# Ak_ll__Ev.net
KiCad netlist of a schematic drawn in Altium Designer
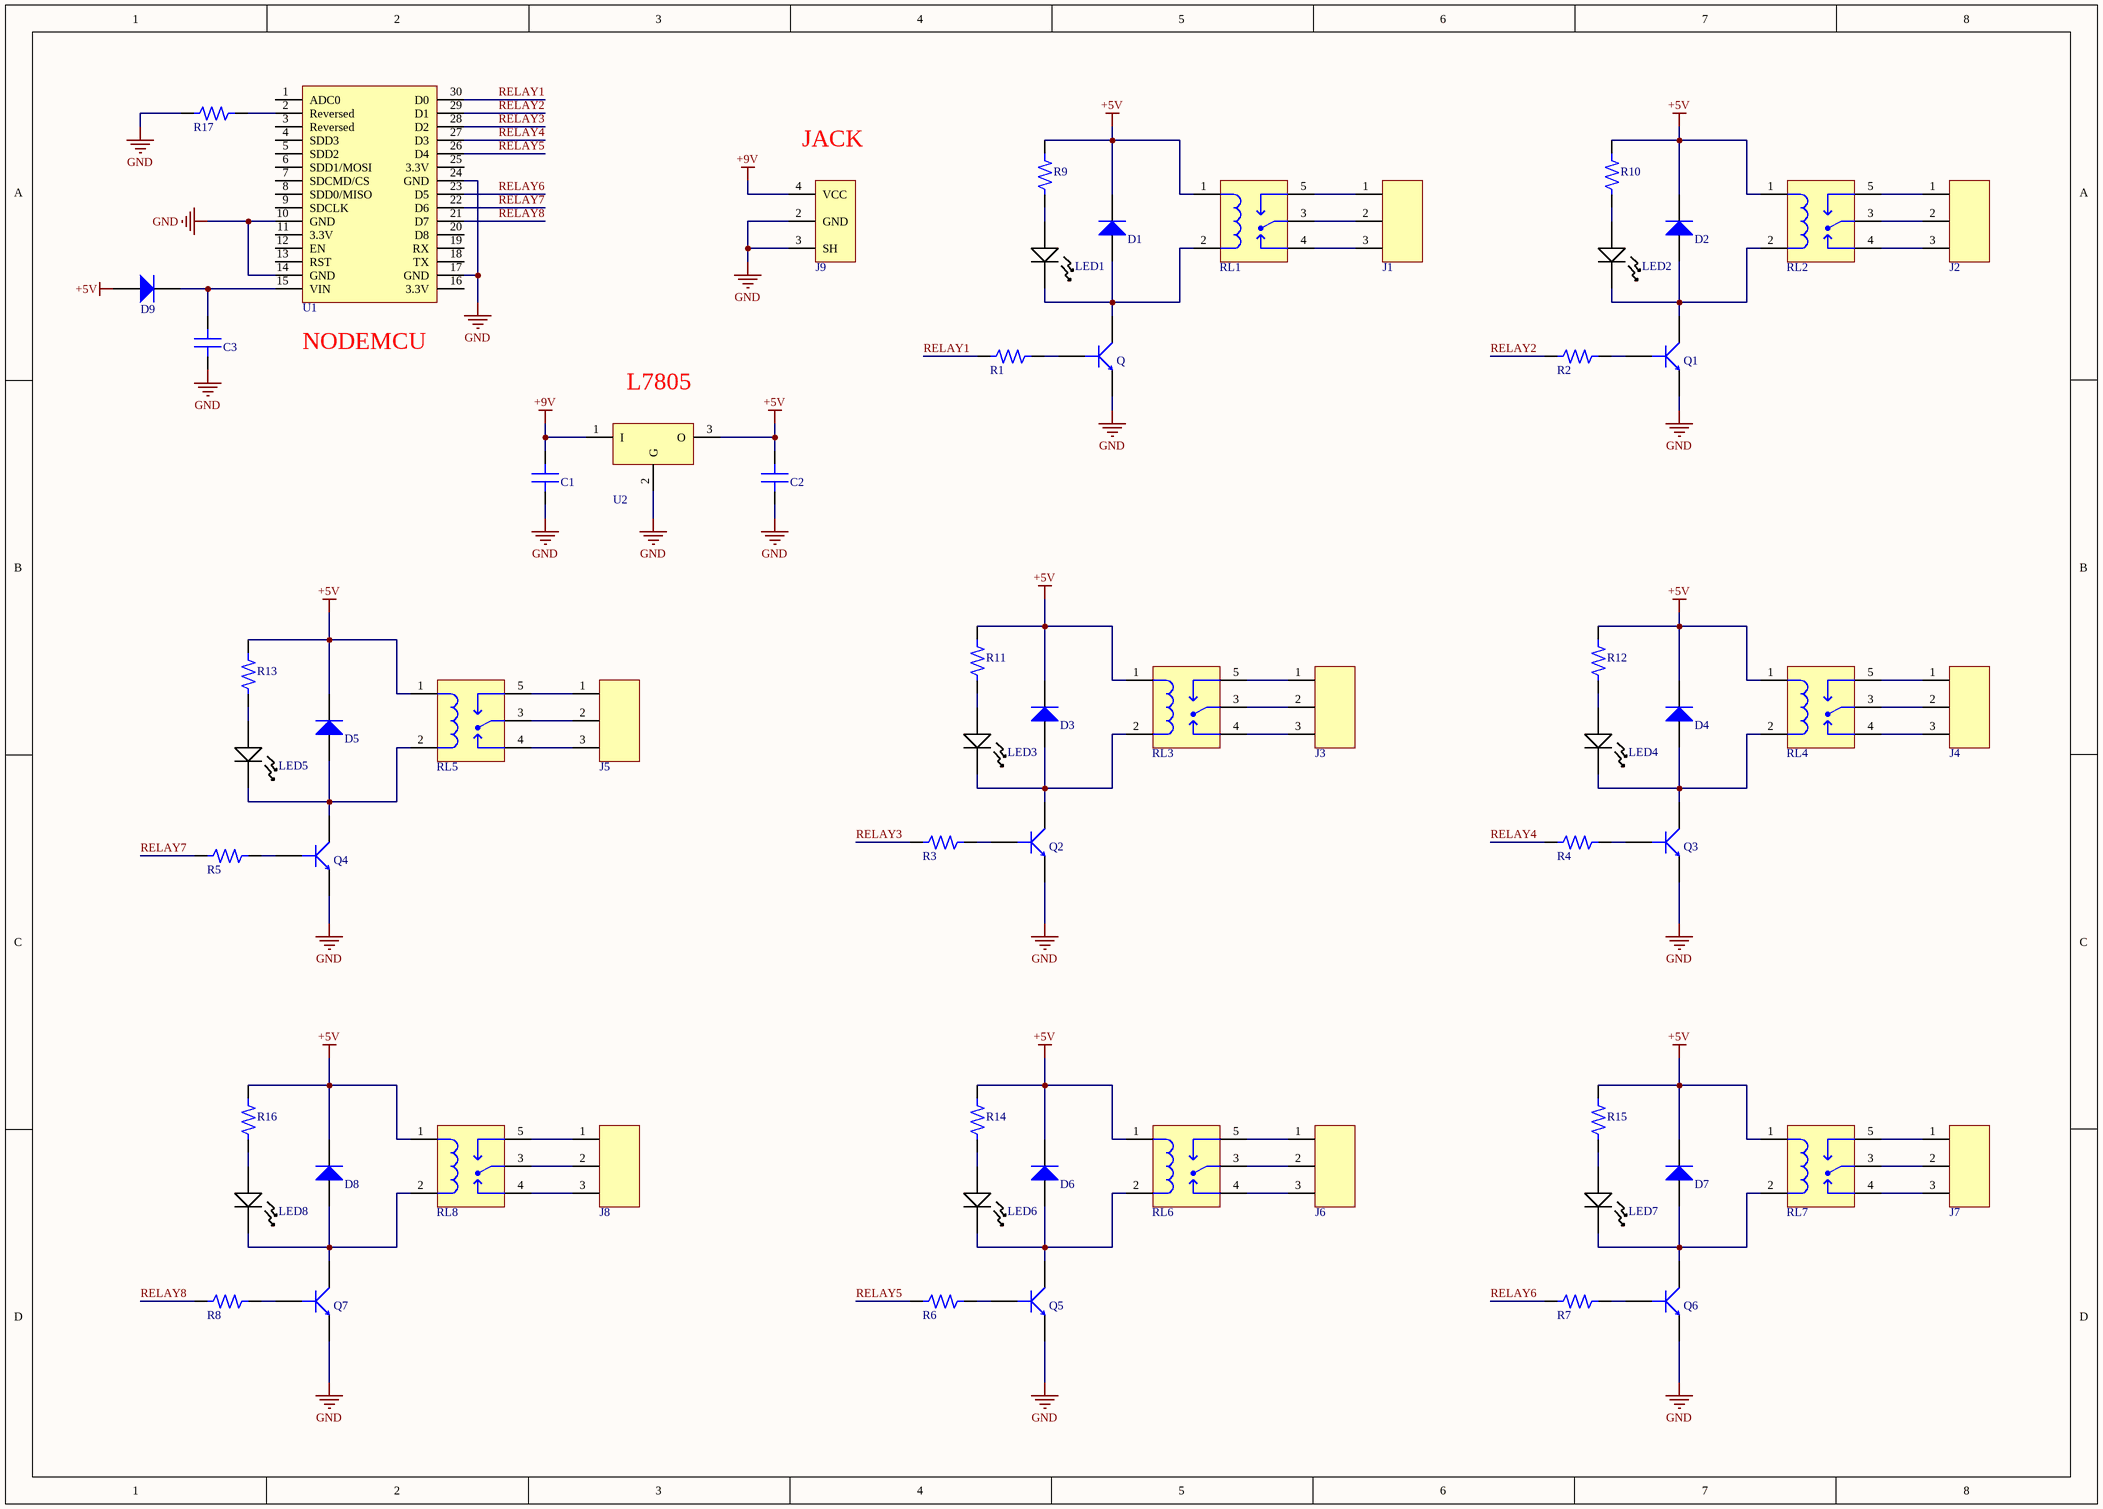
[diagram p0: Akıllı_Ev.SchDoc]

(export (version "E")
  (design (tool "Eeschema 10.0.6"))
  (components
    (comp (ref "C1") (value "100uF") (footprint "CAP 100uF") (libsource (lib "AKILLI_EV") (part "CAP 100uF")))
    (comp (ref "C2") (value "100uF") (footprint "CAP 100uF") (libsource (lib "AKILLI_EV") (part "CAP 100uF")))
    (comp (ref "C3") (value "100nF") (footprint "CAP 100nF") (libsource (lib "AKILLI_EV") (part "CAP 100nF")))
    (comp (ref "D1")
      (value "1N4007")
      (footprint "DIODE - 1N4007")
      (description "1N4007 Rectifier Diode 1 A 1000 V DO-41 Axial 4007 1 amp 1000 Volt Electronic Silicon Diodes")
      (libsource (lib "AKILLI_EV") (part "Diode 1N4007"))
    )
    (comp (ref "D2")
      (value "1N4007")
      (footprint "DIODE - 1N4007")
      (description "1N4007 Rectifier Diode 1 A 1000 V DO-41 Axial 4007 1 amp 1000 Volt Electronic Silicon Diodes")
      (libsource (lib "AKILLI_EV") (part "Diode 1N4007"))
    )
    (comp (ref "D3")
      (value "1N4007")
      (footprint "DIODE - 1N4007")
      (description "1N4007 Rectifier Diode 1 A 1000 V DO-41 Axial 4007 1 amp 1000 Volt Electronic Silicon Diodes")
      (libsource (lib "AKILLI_EV") (part "Diode 1N4007"))
    )
    (comp (ref "D4")
      (value "1N4007")
      (footprint "DIODE - 1N4007")
      (description "1N4007 Rectifier Diode 1 A 1000 V DO-41 Axial 4007 1 amp 1000 Volt Electronic Silicon Diodes")
      (libsource (lib "AKILLI_EV") (part "Diode 1N4007"))
    )
    (comp (ref "D5")
      (value "1N4007")
      (footprint "DIODE - 1N4007")
      (description "1N4007 Rectifier Diode 1 A 1000 V DO-41 Axial 4007 1 amp 1000 Volt Electronic Silicon Diodes")
      (libsource (lib "AKILLI_EV") (part "Diode 1N4007"))
    )
    (comp (ref "D6")
      (value "1N4007")
      (footprint "DIODE - 1N4007")
      (description "1N4007 Rectifier Diode 1 A 1000 V DO-41 Axial 4007 1 amp 1000 Volt Electronic Silicon Diodes")
      (libsource (lib "AKILLI_EV") (part "Diode 1N4007"))
    )
    (comp (ref "D7")
      (value "1N4007")
      (footprint "DIODE - 1N4007")
      (description "1N4007 Rectifier Diode 1 A 1000 V DO-41 Axial 4007 1 amp 1000 Volt Electronic Silicon Diodes")
      (libsource (lib "AKILLI_EV") (part "Diode 1N4007"))
    )
    (comp (ref "D8")
      (value "1N4007")
      (footprint "DIODE - 1N4007")
      (description "1N4007 Rectifier Diode 1 A 1000 V DO-41 Axial 4007 1 amp 1000 Volt Electronic Silicon Diodes")
      (libsource (lib "AKILLI_EV") (part "Diode 1N4007"))
    )
    (comp (ref "D9")
      (value "1N4007")
      (footprint "DIODE - 1N4007")
      (description "1N4007 Rectifier Diode 1 A 1000 V DO-41 Axial 4007 1 amp 1000 Volt Electronic Silicon Diodes")
      (libsource (lib "AKILLI_EV") (part "Diode 1N4007"))
    )
    (comp (ref "J1")
      (value "HEADER x3")
      (footprint "hEADER X3")
      (description "TERM BLK 3POS SIDE ENT 3.5MM PCB")
      (libsource (lib "Schlib1") (part "HEADER x3"))
    )
    (comp (ref "J2")
      (value "HEADER x3")
      (footprint "hEADER X3")
      (description "TERM BLK 3POS SIDE ENT 3.5MM PCB")
      (libsource (lib "Schlib1") (part "HEADER x3"))
    )
    (comp (ref "J3")
      (value "HEADER x3")
      (footprint "hEADER X3")
      (description "TERM BLK 3POS SIDE ENT 3.5MM PCB")
      (libsource (lib "Schlib1") (part "HEADER x3"))
    )
    (comp (ref "J4")
      (value "HEADER x3")
      (footprint "hEADER X3")
      (description "TERM BLK 3POS SIDE ENT 3.5MM PCB")
      (libsource (lib "Schlib1") (part "HEADER x3"))
    )
    (comp (ref "J5")
      (value "HEADER x3")
      (footprint "hEADER X3")
      (description "TERM BLK 3POS SIDE ENT 3.5MM PCB")
      (libsource (lib "Schlib1") (part "HEADER x3"))
    )
    (comp (ref "J6")
      (value "HEADER x3")
      (footprint "hEADER X3")
      (description "TERM BLK 3POS SIDE ENT 3.5MM PCB")
      (libsource (lib "Schlib1") (part "HEADER x3"))
    )
    (comp (ref "J7")
      (value "HEADER x3")
      (footprint "hEADER X3")
      (description "TERM BLK 3POS SIDE ENT 3.5MM PCB")
      (libsource (lib "Schlib1") (part "HEADER x3"))
    )
    (comp (ref "J8")
      (value "HEADER x3")
      (footprint "hEADER X3")
      (description "TERM BLK 3POS SIDE ENT 3.5MM PCB")
      (libsource (lib "Schlib1") (part "HEADER x3"))
    )
    (comp (ref "J9")
      (value "JACK")
      (footprint "JACK")
      (description "5.5 x 2.1 mm DC güç jak soketi")
      (libsource (lib "AKILLI_EV") (part "JACK"))
    )
    (comp (ref "LED1") (value "LED RED") (footprint "LED") (libsource (lib "AKILLI_EV") (part "LED RED")))
    (comp (ref "LED2") (value "LED RED") (footprint "LED") (libsource (lib "AKILLI_EV") (part "LED RED")))
    (comp (ref "LED3") (value "LED RED") (footprint "LED") (libsource (lib "AKILLI_EV") (part "LED RED")))
    (comp (ref "LED4") (value "LED RED") (footprint "LED") (libsource (lib "AKILLI_EV") (part "LED RED")))
    (comp (ref "LED5") (value "LED RED") (footprint "LED") (libsource (lib "AKILLI_EV") (part "LED RED")))
    (comp (ref "LED6") (value "LED RED") (footprint "LED") (libsource (lib "AKILLI_EV") (part "LED RED")))
    (comp (ref "LED7") (value "LED RED") (footprint "LED") (libsource (lib "AKILLI_EV") (part "LED RED")))
    (comp (ref "LED8") (value "LED RED") (footprint "LED") (libsource (lib "AKILLI_EV") (part "LED RED")))
    (comp (ref "Q")
      (value "BC547")
      (footprint "BC547 - NPN")
      (description "NPN Transistor BC547")
      (libsource (lib "AKILLI_EV") (part "NPN Transistor BC547"))
    )
    (comp (ref "Q1")
      (value "BC547")
      (footprint "BC547 - NPN")
      (description "NPN Transistor BC547")
      (libsource (lib "AKILLI_EV") (part "NPN Transistor BC547"))
    )
    (comp (ref "Q2")
      (value "BC547")
      (footprint "BC547 - NPN")
      (description "NPN Transistor BC547")
      (libsource (lib "AKILLI_EV") (part "NPN Transistor BC547"))
    )
    (comp (ref "Q3")
      (value "BC547")
      (footprint "BC547 - NPN")
      (description "NPN Transistor BC547")
      (libsource (lib "AKILLI_EV") (part "NPN Transistor BC547"))
    )
    (comp (ref "Q4")
      (value "BC547")
      (footprint "BC547 - NPN")
      (description "NPN Transistor BC547")
      (libsource (lib "AKILLI_EV") (part "NPN Transistor BC547"))
    )
    (comp (ref "Q5")
      (value "BC547")
      (footprint "BC547 - NPN")
      (description "NPN Transistor BC547")
      (libsource (lib "AKILLI_EV") (part "NPN Transistor BC547"))
    )
    (comp (ref "Q6")
      (value "BC547")
      (footprint "BC547 - NPN")
      (description "NPN Transistor BC547")
      (libsource (lib "AKILLI_EV") (part "NPN Transistor BC547"))
    )
    (comp (ref "Q7")
      (value "BC547")
      (footprint "BC547 - NPN")
      (description "NPN Transistor BC547")
      (libsource (lib "AKILLI_EV") (part "NPN Transistor BC547"))
    )
    (comp (ref "R1")
      (value "RES 1K OHM")
      (footprint "RES 1K OHM")
      (description "Resistor thru-hole Axial 0.4")
      (libsource (lib "AKILLI_EV") (part "RES 1K OHM"))
    )
    (comp (ref "R2")
      (value "RES 1K OHM")
      (footprint "RES 1K OHM")
      (description "Resistor thru-hole Axial 0.4")
      (libsource (lib "AKILLI_EV") (part "RES 1K OHM"))
    )
    (comp (ref "R3")
      (value "RES 1K OHM")
      (footprint "RES 1K OHM")
      (description "Resistor thru-hole Axial 0.4")
      (libsource (lib "AKILLI_EV") (part "RES 1K OHM"))
    )
    (comp (ref "R4")
      (value "RES 1K OHM")
      (footprint "RES 1K OHM")
      (description "Resistor thru-hole Axial 0.4")
      (libsource (lib "AKILLI_EV") (part "RES 1K OHM"))
    )
    (comp (ref "R5")
      (value "RES 1K OHM")
      (footprint "RES 1K OHM")
      (description "Resistor thru-hole Axial 0.4")
      (libsource (lib "AKILLI_EV") (part "RES 1K OHM"))
    )
    (comp (ref "R6")
      (value "RES 1K OHM")
      (footprint "RES 1K OHM")
      (description "Resistor thru-hole Axial 0.4")
      (libsource (lib "AKILLI_EV") (part "RES 1K OHM"))
    )
    (comp (ref "R7")
      (value "RES 1K OHM")
      (footprint "RES 1K OHM")
      (description "Resistor thru-hole Axial 0.4")
      (libsource (lib "AKILLI_EV") (part "RES 1K OHM"))
    )
    (comp (ref "R8")
      (value "RES 1K OHM")
      (footprint "RES 1K OHM")
      (description "Resistor thru-hole Axial 0.4")
      (libsource (lib "AKILLI_EV") (part "RES 1K OHM"))
    )
    (comp (ref "R9")
      (value "RES 470 OHM")
      (footprint "RES 470 OHM")
      (description "Resistor thru-hole Axial 0.4")
      (libsource (lib "AKILLI_EV") (part "RES 470 OHM"))
    )
    (comp (ref "R10")
      (value "RES 470 OHM")
      (footprint "RES 470 OHM")
      (description "Resistor thru-hole Axial 0.4")
      (libsource (lib "AKILLI_EV") (part "RES 470 OHM"))
    )
    (comp (ref "R11")
      (value "RES 470 OHM")
      (footprint "RES 470 OHM")
      (description "Resistor thru-hole Axial 0.4")
      (libsource (lib "AKILLI_EV") (part "RES 470 OHM"))
    )
    (comp (ref "R12")
      (value "RES 470 OHM")
      (footprint "RES 470 OHM")
      (description "Resistor thru-hole Axial 0.4")
      (libsource (lib "AKILLI_EV") (part "RES 470 OHM"))
    )
    (comp (ref "R13")
      (value "RES 470 OHM")
      (footprint "RES 470 OHM")
      (description "Resistor thru-hole Axial 0.4")
      (libsource (lib "AKILLI_EV") (part "RES 470 OHM"))
    )
    (comp (ref "R14")
      (value "RES 470 OHM")
      (footprint "RES 470 OHM")
      (description "Resistor thru-hole Axial 0.4")
      (libsource (lib "AKILLI_EV") (part "RES 470 OHM"))
    )
    (comp (ref "R15")
      (value "RES 470 OHM")
      (footprint "RES 470 OHM")
      (description "Resistor thru-hole Axial 0.4")
      (libsource (lib "AKILLI_EV") (part "RES 470 OHM"))
    )
    (comp (ref "R16")
      (value "RES 470 OHM")
      (footprint "RES 470 OHM")
      (description "Resistor thru-hole Axial 0.4")
      (libsource (lib "AKILLI_EV") (part "RES 470 OHM"))
    )
    (comp (ref "R17")
      (value "RES 0603")
      (footprint "RES 0603")
      (libsource (lib "AKILLI_EV") (part "RES 0603"))
    )
    (comp (ref "RL1")
      (value "Relay")
      (footprint "RELAY")
      (description "SPDT 5V RELAY")
      (libsource (lib "Schlib1") (part "Relay"))
    )
    (comp (ref "RL2")
      (value "Relay")
      (footprint "RELAY")
      (description "SPDT 5V RELAY")
      (libsource (lib "Schlib1") (part "Relay"))
    )
    (comp (ref "RL3")
      (value "Relay")
      (footprint "RELAY")
      (description "SPDT 5V RELAY")
      (libsource (lib "Schlib1") (part "Relay"))
    )
    (comp (ref "RL4")
      (value "Relay")
      (footprint "RELAY")
      (description "SPDT 5V RELAY")
      (libsource (lib "Schlib1") (part "Relay"))
    )
    (comp (ref "RL5")
      (value "Relay")
      (footprint "RELAY")
      (description "SPDT 5V RELAY")
      (libsource (lib "Schlib1") (part "Relay"))
    )
    (comp (ref "RL6")
      (value "Relay")
      (footprint "RELAY")
      (description "SPDT 5V RELAY")
      (libsource (lib "Schlib1") (part "Relay"))
    )
    (comp (ref "RL7")
      (value "Relay")
      (footprint "RELAY")
      (description "SPDT 5V RELAY")
      (libsource (lib "Schlib1") (part "Relay"))
    )
    (comp (ref "RL8")
      (value "Relay")
      (footprint "RELAY")
      (description "SPDT 5V RELAY")
      (libsource (lib "Schlib1") (part "Relay"))
    )
    (comp (ref "U1")
      (value "NodeMCU-ESP8266")
      (footprint "NodeMCU-ESP8266")
      (libsource (lib "AKILLI_EV") (part "NodeMCU-ESP8266"))
    )
    (comp (ref "U2")
      (value "L7805")
      (footprint "L7805")
      (description "5V REG")
      (libsource (lib "Schlib1") (part "L7805"))
    )
  )
  (nets
    (net (code "1") (name "+5V") (class "Default")
      (node (ref "C2") (pin "2") (pinfunction "2_2") (pintype "passive"))
      (node (ref "D1") (pin "2") (pinfunction "CATHODE_2") (pintype "passive"))
      (node (ref "D2") (pin "2") (pinfunction "CATHODE_2") (pintype "passive"))
      (node (ref "D3") (pin "2") (pinfunction "CATHODE_2") (pintype "passive"))
      (node (ref "D4") (pin "2") (pinfunction "CATHODE_2") (pintype "passive"))
      (node (ref "D5") (pin "2") (pinfunction "CATHODE_2") (pintype "passive"))
      (node (ref "D6") (pin "2") (pinfunction "CATHODE_2") (pintype "passive"))
      (node (ref "D7") (pin "2") (pinfunction "CATHODE_2") (pintype "passive"))
      (node (ref "D8") (pin "2") (pinfunction "CATHODE_2") (pintype "passive"))
      (node (ref "D9") (pin "1") (pinfunction "ANODE_1") (pintype "passive"))
      (node (ref "R10") (pin "2") (pinfunction "2_2") (pintype "passive"))
      (node (ref "R11") (pin "2") (pinfunction "2_2") (pintype "passive"))
      (node (ref "R12") (pin "2") (pinfunction "2_2") (pintype "passive"))
      (node (ref "R13") (pin "2") (pinfunction "2_2") (pintype "passive"))
      (node (ref "R14") (pin "2") (pinfunction "2_2") (pintype "passive"))
      (node (ref "R15") (pin "2") (pinfunction "2_2") (pintype "passive"))
      (node (ref "R16") (pin "2") (pinfunction "2_2") (pintype "passive"))
      (node (ref "R9") (pin "2") (pinfunction "2_2") (pintype "passive"))
      (node (ref "RL1") (pin "1") (pinfunction "1_1") (pintype "passive"))
      (node (ref "RL2") (pin "1") (pinfunction "1_1") (pintype "passive"))
      (node (ref "RL3") (pin "1") (pinfunction "1_1") (pintype "passive"))
      (node (ref "RL4") (pin "1") (pinfunction "1_1") (pintype "passive"))
      (node (ref "RL5") (pin "1") (pinfunction "1_1") (pintype "passive"))
      (node (ref "RL6") (pin "1") (pinfunction "1_1") (pintype "passive"))
      (node (ref "RL7") (pin "1") (pinfunction "1_1") (pintype "passive"))
      (node (ref "RL8") (pin "1") (pinfunction "1_1") (pintype "passive"))
      (node (ref "U2") (pin "3") (pinfunction "O_3") (pintype "passive"))
    )
    (net (code "2") (name "+9V") (class "Default")
      (node (ref "C1") (pin "2") (pinfunction "2_2") (pintype "passive"))
      (node (ref "J9") (pin "4") (pinfunction "VCC_4") (pintype "power_in"))
      (node (ref "U2") (pin "1") (pinfunction "I_1") (pintype "passive"))
    )
    (net (code "3") (name "/RELAY1") (class "Default")
      (node (ref "R1") (pin "1") (pinfunction "1_1") (pintype "passive"))
      (node (ref "U1") (pin "30") (pinfunction "D0_30") (pintype "passive"))
    )
    (net (code "4") (name "/RELAY2") (class "Default")
      (node (ref "R2") (pin "1") (pinfunction "1_1") (pintype "passive"))
      (node (ref "U1") (pin "29") (pinfunction "D1_29") (pintype "passive"))
    )
    (net (code "5") (name "/RELAY3") (class "Default")
      (node (ref "R3") (pin "1") (pinfunction "1_1") (pintype "passive"))
      (node (ref "U1") (pin "28") (pinfunction "D2_28") (pintype "passive"))
    )
    (net (code "6") (name "/RELAY4") (class "Default")
      (node (ref "R4") (pin "1") (pinfunction "1_1") (pintype "passive"))
      (node (ref "U1") (pin "27") (pinfunction "D3_27") (pintype "passive"))
    )
    (net (code "7") (name "/RELAY5") (class "Default")
      (node (ref "R6") (pin "1") (pinfunction "1_1") (pintype "passive"))
      (node (ref "U1") (pin "26") (pinfunction "D4_26") (pintype "passive"))
    )
    (net (code "8") (name "/RELAY6") (class "Default")
      (node (ref "R7") (pin "1") (pinfunction "1_1") (pintype "passive"))
      (node (ref "U1") (pin "23") (pinfunction "D5_23") (pintype "passive"))
    )
    (net (code "9") (name "/RELAY7") (class "Default")
      (node (ref "R5") (pin "1") (pinfunction "1_1") (pintype "passive"))
      (node (ref "U1") (pin "22") (pinfunction "D6_22") (pintype "passive"))
    )
    (net (code "10") (name "/RELAY8") (class "Default")
      (node (ref "R8") (pin "1") (pinfunction "1_1") (pintype "passive"))
      (node (ref "U1") (pin "21") (pinfunction "D7_21") (pintype "passive"))
    )
    (net (code "11") (name "GND") (class "Default")
      (node (ref "C1") (pin "1") (pinfunction "1_1") (pintype "passive"))
      (node (ref "C2") (pin "1") (pinfunction "1_1") (pintype "passive"))
      (node (ref "C3") (pin "1") (pinfunction "1_1") (pintype "passive"))
      (node (ref "J9") (pin "2") (pinfunction "GND_2") (pintype "power_in"))
      (node (ref "J9") (pin "3") (pinfunction "SH_3") (pintype "power_in"))
      (node (ref "Q") (pin "2") (pinfunction "E_2") (pintype "passive"))
      (node (ref "Q1") (pin "2") (pinfunction "E_2") (pintype "passive"))
      (node (ref "Q2") (pin "2") (pinfunction "E_2") (pintype "passive"))
      (node (ref "Q3") (pin "2") (pinfunction "E_2") (pintype "passive"))
      (node (ref "Q4") (pin "2") (pinfunction "E_2") (pintype "passive"))
      (node (ref "Q5") (pin "2") (pinfunction "E_2") (pintype "passive"))
      (node (ref "Q6") (pin "2") (pinfunction "E_2") (pintype "passive"))
      (node (ref "Q7") (pin "2") (pinfunction "E_2") (pintype "passive"))
      (node (ref "R17") (pin "1") (pinfunction "1_1") (pintype "passive"))
      (node (ref "U1") (pin "10") (pinfunction "GND_10") (pintype "passive"))
      (node (ref "U1") (pin "14") (pinfunction "GND_14") (pintype "passive"))
      (node (ref "U1") (pin "17") (pinfunction "GND_17") (pintype "passive"))
      (node (ref "U1") (pin "24") (pinfunction "GND_24") (pintype "passive"))
      (node (ref "U2") (pin "2") (pinfunction "G_2") (pintype "passive"))
    )
    (net (code "12") (name "Net-(D1-ANODE)") (class "Default")
      (node (ref "D1") (pin "1") (pinfunction "ANODE_1") (pintype "passive"))
      (node (ref "LED1") (pin "2") (pinfunction "2_2") (pintype "passive"))
      (node (ref "Q") (pin "3") (pinfunction "C_3") (pintype "passive"))
      (node (ref "RL1") (pin "2") (pinfunction "2_2") (pintype "passive"))
    )
    (net (code "13") (name "Net-(D2-ANODE)") (class "Default")
      (node (ref "D2") (pin "1") (pinfunction "ANODE_1") (pintype "passive"))
      (node (ref "LED2") (pin "2") (pinfunction "2_2") (pintype "passive"))
      (node (ref "Q1") (pin "3") (pinfunction "C_3") (pintype "passive"))
      (node (ref "RL2") (pin "2") (pinfunction "2_2") (pintype "passive"))
    )
    (net (code "14") (name "Net-(D3-ANODE)") (class "Default")
      (node (ref "D3") (pin "1") (pinfunction "ANODE_1") (pintype "passive"))
      (node (ref "LED3") (pin "2") (pinfunction "2_2") (pintype "passive"))
      (node (ref "Q2") (pin "3") (pinfunction "C_3") (pintype "passive"))
      (node (ref "RL3") (pin "2") (pinfunction "2_2") (pintype "passive"))
    )
    (net (code "15") (name "Net-(D4-ANODE)") (class "Default")
      (node (ref "D4") (pin "1") (pinfunction "ANODE_1") (pintype "passive"))
      (node (ref "LED4") (pin "2") (pinfunction "2_2") (pintype "passive"))
      (node (ref "Q3") (pin "3") (pinfunction "C_3") (pintype "passive"))
      (node (ref "RL4") (pin "2") (pinfunction "2_2") (pintype "passive"))
    )
    (net (code "16") (name "Net-(D5-ANODE)") (class "Default")
      (node (ref "D5") (pin "1") (pinfunction "ANODE_1") (pintype "passive"))
      (node (ref "LED5") (pin "2") (pinfunction "2_2") (pintype "passive"))
      (node (ref "Q4") (pin "3") (pinfunction "C_3") (pintype "passive"))
      (node (ref "RL5") (pin "2") (pinfunction "2_2") (pintype "passive"))
    )
    (net (code "17") (name "Net-(D6-ANODE)") (class "Default")
      (node (ref "D6") (pin "1") (pinfunction "ANODE_1") (pintype "passive"))
      (node (ref "LED6") (pin "2") (pinfunction "2_2") (pintype "passive"))
      (node (ref "Q5") (pin "3") (pinfunction "C_3") (pintype "passive"))
      (node (ref "RL6") (pin "2") (pinfunction "2_2") (pintype "passive"))
    )
    (net (code "18") (name "Net-(D7-ANODE)") (class "Default")
      (node (ref "D7") (pin "1") (pinfunction "ANODE_1") (pintype "passive"))
      (node (ref "LED7") (pin "2") (pinfunction "2_2") (pintype "passive"))
      (node (ref "Q6") (pin "3") (pinfunction "C_3") (pintype "passive"))
      (node (ref "RL7") (pin "2") (pinfunction "2_2") (pintype "passive"))
    )
    (net (code "19") (name "Net-(D8-ANODE)") (class "Default")
      (node (ref "D8") (pin "1") (pinfunction "ANODE_1") (pintype "passive"))
      (node (ref "LED8") (pin "2") (pinfunction "2_2") (pintype "passive"))
      (node (ref "Q7") (pin "3") (pinfunction "C_3") (pintype "passive"))
      (node (ref "RL8") (pin "2") (pinfunction "2_2") (pintype "passive"))
    )
    (net (code "20") (name "Net-(D9-CATHODE)") (class "Default")
      (node (ref "C3") (pin "2") (pinfunction "2_2") (pintype "passive"))
      (node (ref "D9") (pin "2") (pinfunction "CATHODE_2") (pintype "passive"))
      (node (ref "U1") (pin "15") (pinfunction "VIN_15") (pintype "passive"))
    )
    (net (code "21") (name "Net-(J1-Pad1)") (class "Default")
      (node (ref "J1") (pin "1") (pinfunction "1_1") (pintype "passive"))
      (node (ref "RL1") (pin "5") (pinfunction "5_5") (pintype "passive"))
    )
    (net (code "22") (name "Net-(J1-Pad2)") (class "Default")
      (node (ref "J1") (pin "2") (pinfunction "2_2") (pintype "passive"))
      (node (ref "RL1") (pin "3") (pinfunction "3_3") (pintype "passive"))
    )
    (net (code "23") (name "Net-(J1-Pad3)") (class "Default")
      (node (ref "J1") (pin "3") (pinfunction "3_3") (pintype "passive"))
      (node (ref "RL1") (pin "4") (pinfunction "4_4") (pintype "passive"))
    )
    (net (code "24") (name "Net-(J2-Pad1)") (class "Default")
      (node (ref "J2") (pin "1") (pinfunction "1_1") (pintype "passive"))
      (node (ref "RL2") (pin "5") (pinfunction "5_5") (pintype "passive"))
    )
    (net (code "25") (name "Net-(J2-Pad2)") (class "Default")
      (node (ref "J2") (pin "2") (pinfunction "2_2") (pintype "passive"))
      (node (ref "RL2") (pin "3") (pinfunction "3_3") (pintype "passive"))
    )
    (net (code "26") (name "Net-(J2-Pad3)") (class "Default")
      (node (ref "J2") (pin "3") (pinfunction "3_3") (pintype "passive"))
      (node (ref "RL2") (pin "4") (pinfunction "4_4") (pintype "passive"))
    )
    (net (code "27") (name "Net-(J3-Pad1)") (class "Default")
      (node (ref "J3") (pin "1") (pinfunction "1_1") (pintype "passive"))
      (node (ref "RL3") (pin "5") (pinfunction "5_5") (pintype "passive"))
    )
    (net (code "28") (name "Net-(J3-Pad2)") (class "Default")
      (node (ref "J3") (pin "2") (pinfunction "2_2") (pintype "passive"))
      (node (ref "RL3") (pin "3") (pinfunction "3_3") (pintype "passive"))
    )
    (net (code "29") (name "Net-(J3-Pad3)") (class "Default")
      (node (ref "J3") (pin "3") (pinfunction "3_3") (pintype "passive"))
      (node (ref "RL3") (pin "4") (pinfunction "4_4") (pintype "passive"))
    )
    (net (code "30") (name "Net-(J4-Pad1)") (class "Default")
      (node (ref "J4") (pin "1") (pinfunction "1_1") (pintype "passive"))
      (node (ref "RL4") (pin "5") (pinfunction "5_5") (pintype "passive"))
    )
    (net (code "31") (name "Net-(J4-Pad2)") (class "Default")
      (node (ref "J4") (pin "2") (pinfunction "2_2") (pintype "passive"))
      (node (ref "RL4") (pin "3") (pinfunction "3_3") (pintype "passive"))
    )
    (net (code "32") (name "Net-(J4-Pad3)") (class "Default")
      (node (ref "J4") (pin "3") (pinfunction "3_3") (pintype "passive"))
      (node (ref "RL4") (pin "4") (pinfunction "4_4") (pintype "passive"))
    )
    (net (code "33") (name "Net-(J5-Pad1)") (class "Default")
      (node (ref "J5") (pin "1") (pinfunction "1_1") (pintype "passive"))
      (node (ref "RL5") (pin "5") (pinfunction "5_5") (pintype "passive"))
    )
    (net (code "34") (name "Net-(J5-Pad2)") (class "Default")
      (node (ref "J5") (pin "2") (pinfunction "2_2") (pintype "passive"))
      (node (ref "RL5") (pin "3") (pinfunction "3_3") (pintype "passive"))
    )
    (net (code "35") (name "Net-(J5-Pad3)") (class "Default")
      (node (ref "J5") (pin "3") (pinfunction "3_3") (pintype "passive"))
      (node (ref "RL5") (pin "4") (pinfunction "4_4") (pintype "passive"))
    )
    (net (code "36") (name "Net-(J6-Pad1)") (class "Default")
      (node (ref "J6") (pin "1") (pinfunction "1_1") (pintype "passive"))
      (node (ref "RL6") (pin "5") (pinfunction "5_5") (pintype "passive"))
    )
    (net (code "37") (name "Net-(J6-Pad2)") (class "Default")
      (node (ref "J6") (pin "2") (pinfunction "2_2") (pintype "passive"))
      (node (ref "RL6") (pin "3") (pinfunction "3_3") (pintype "passive"))
    )
    (net (code "38") (name "Net-(J6-Pad3)") (class "Default")
      (node (ref "J6") (pin "3") (pinfunction "3_3") (pintype "passive"))
      (node (ref "RL6") (pin "4") (pinfunction "4_4") (pintype "passive"))
    )
    (net (code "39") (name "Net-(J7-Pad1)") (class "Default")
      (node (ref "J7") (pin "1") (pinfunction "1_1") (pintype "passive"))
      (node (ref "RL7") (pin "5") (pinfunction "5_5") (pintype "passive"))
    )
    (net (code "40") (name "Net-(J7-Pad2)") (class "Default")
      (node (ref "J7") (pin "2") (pinfunction "2_2") (pintype "passive"))
      (node (ref "RL7") (pin "3") (pinfunction "3_3") (pintype "passive"))
    )
    (net (code "41") (name "Net-(J7-Pad3)") (class "Default")
      (node (ref "J7") (pin "3") (pinfunction "3_3") (pintype "passive"))
      (node (ref "RL7") (pin "4") (pinfunction "4_4") (pintype "passive"))
    )
    (net (code "42") (name "Net-(J8-Pad1)") (class "Default")
      (node (ref "J8") (pin "1") (pinfunction "1_1") (pintype "passive"))
      (node (ref "RL8") (pin "5") (pinfunction "5_5") (pintype "passive"))
    )
    (net (code "43") (name "Net-(J8-Pad2)") (class "Default")
      (node (ref "J8") (pin "2") (pinfunction "2_2") (pintype "passive"))
      (node (ref "RL8") (pin "3") (pinfunction "3_3") (pintype "passive"))
    )
    (net (code "44") (name "Net-(J8-Pad3)") (class "Default")
      (node (ref "J8") (pin "3") (pinfunction "3_3") (pintype "passive"))
      (node (ref "RL8") (pin "4") (pinfunction "4_4") (pintype "passive"))
    )
    (net (code "45") (name "Net-(LED1-Pad1)") (class "Default")
      (node (ref "LED1") (pin "1") (pinfunction "1_1") (pintype "passive"))
      (node (ref "R9") (pin "1") (pinfunction "1_1") (pintype "passive"))
    )
    (net (code "46") (name "Net-(LED2-Pad1)") (class "Default")
      (node (ref "LED2") (pin "1") (pinfunction "1_1") (pintype "passive"))
      (node (ref "R10") (pin "1") (pinfunction "1_1") (pintype "passive"))
    )
    (net (code "47") (name "Net-(LED3-Pad1)") (class "Default")
      (node (ref "LED3") (pin "1") (pinfunction "1_1") (pintype "passive"))
      (node (ref "R11") (pin "1") (pinfunction "1_1") (pintype "passive"))
    )
    (net (code "48") (name "Net-(LED4-Pad1)") (class "Default")
      (node (ref "LED4") (pin "1") (pinfunction "1_1") (pintype "passive"))
      (node (ref "R12") (pin "1") (pinfunction "1_1") (pintype "passive"))
    )
    (net (code "49") (name "Net-(LED5-Pad1)") (class "Default")
      (node (ref "LED5") (pin "1") (pinfunction "1_1") (pintype "passive"))
      (node (ref "R13") (pin "1") (pinfunction "1_1") (pintype "passive"))
    )
    (net (code "50") (name "Net-(LED6-Pad1)") (class "Default")
      (node (ref "LED6") (pin "1") (pinfunction "1_1") (pintype "passive"))
      (node (ref "R14") (pin "1") (pinfunction "1_1") (pintype "passive"))
    )
    (net (code "51") (name "Net-(LED7-Pad1)") (class "Default")
      (node (ref "LED7") (pin "1") (pinfunction "1_1") (pintype "passive"))
      (node (ref "R15") (pin "1") (pinfunction "1_1") (pintype "passive"))
    )
    (net (code "52") (name "Net-(LED8-Pad1)") (class "Default")
      (node (ref "LED8") (pin "1") (pinfunction "1_1") (pintype "passive"))
      (node (ref "R16") (pin "1") (pinfunction "1_1") (pintype "passive"))
    )
    (net (code "53") (name "Net-(Q-B)") (class "Default")
      (node (ref "Q") (pin "1") (pinfunction "B_1") (pintype "passive"))
      (node (ref "R1") (pin "2") (pinfunction "2_2") (pintype "passive"))
    )
    (net (code "54") (name "Net-(Q1-B)") (class "Default")
      (node (ref "Q1") (pin "1") (pinfunction "B_1") (pintype "passive"))
      (node (ref "R2") (pin "2") (pinfunction "2_2") (pintype "passive"))
    )
    (net (code "55") (name "Net-(Q2-B)") (class "Default")
      (node (ref "Q2") (pin "1") (pinfunction "B_1") (pintype "passive"))
      (node (ref "R3") (pin "2") (pinfunction "2_2") (pintype "passive"))
    )
    (net (code "56") (name "Net-(Q3-B)") (class "Default")
      (node (ref "Q3") (pin "1") (pinfunction "B_1") (pintype "passive"))
      (node (ref "R4") (pin "2") (pinfunction "2_2") (pintype "passive"))
    )
    (net (code "57") (name "Net-(Q4-B)") (class "Default")
      (node (ref "Q4") (pin "1") (pinfunction "B_1") (pintype "passive"))
      (node (ref "R5") (pin "2") (pinfunction "2_2") (pintype "passive"))
    )
    (net (code "58") (name "Net-(Q5-B)") (class "Default")
      (node (ref "Q5") (pin "1") (pinfunction "B_1") (pintype "passive"))
      (node (ref "R6") (pin "2") (pinfunction "2_2") (pintype "passive"))
    )
    (net (code "59") (name "Net-(Q6-B)") (class "Default")
      (node (ref "Q6") (pin "1") (pinfunction "B_1") (pintype "passive"))
      (node (ref "R7") (pin "2") (pinfunction "2_2") (pintype "passive"))
    )
    (net (code "60") (name "Net-(Q7-B)") (class "Default")
      (node (ref "Q7") (pin "1") (pinfunction "B_1") (pintype "passive"))
      (node (ref "R8") (pin "2") (pinfunction "2_2") (pintype "passive"))
    )
    (net (code "61") (name "Net-(R17-Pad2)") (class "Default")
      (node (ref "R17") (pin "2") (pinfunction "2_2") (pintype "passive"))
      (node (ref "U1") (pin "2") (pinfunction "Reversed_2") (pintype "passive"))
    )
    (net (code "62") (name "unconnected-(U1-3.3V-Pad11)") (class "Default")
      (node (ref "U1") (pin "11") (pinfunction "3.3V_11") (pintype "passive"))
    )
    (net (code "63") (name "unconnected-(U1-3.3V-Pad16)") (class "Default")
      (node (ref "U1") (pin "16") (pinfunction "3.3V_16") (pintype "passive"))
    )
    (net (code "64") (name "unconnected-(U1-3.3V-Pad25)") (class "Default")
      (node (ref "U1") (pin "25") (pinfunction "3.3V_25") (pintype "passive"))
    )
    (net (code "65") (name "unconnected-(U1-ADC0-Pad1)") (class "Default")
      (node (ref "U1") (pin "1") (pinfunction "ADC0_1") (pintype "passive"))
    )
    (net (code "66") (name "unconnected-(U1-D8-Pad20)") (class "Default")
      (node (ref "U1") (pin "20") (pinfunction "D8_20") (pintype "passive"))
    )
    (net (code "67") (name "unconnected-(U1-EN-Pad12)") (class "Default")
      (node (ref "U1") (pin "12") (pinfunction "EN_12") (pintype "passive"))
    )
    (net (code "68") (name "unconnected-(U1-RST-Pad13)") (class "Default")
      (node (ref "U1") (pin "13") (pinfunction "RST_13") (pintype "passive"))
    )
    (net (code "69") (name "unconnected-(U1-RX-Pad19)") (class "Default")
      (node (ref "U1") (pin "19") (pinfunction "RX_19") (pintype "passive"))
    )
    (net (code "70") (name "unconnected-(U1-Reversed-Pad3)") (class "Default")
      (node (ref "U1") (pin "3") (pinfunction "Reversed_3") (pintype "passive"))
    )
    (net (code "71") (name "unconnected-(U1-SDCLK-Pad9)") (class "Default")
      (node (ref "U1") (pin "9") (pinfunction "SDCLK_9") (pintype "passive"))
    )
    (net (code "72") (name "unconnected-(U1-SDCMD{slash}CS-Pad7)") (class "Default")
      (node (ref "U1") (pin "7") (pinfunction "SDCMD/CS_7") (pintype "passive"))
    )
    (net (code "73") (name "unconnected-(U1-SDD0{slash}MISO-Pad8)") (class "Default")
      (node (ref "U1") (pin "8") (pinfunction "SDD0/MISO_8") (pintype "passive"))
    )
    (net (code "74") (name "unconnected-(U1-SDD1{slash}MOSI-Pad6)") (class "Default")
      (node (ref "U1") (pin "6") (pinfunction "SDD1/MOSI_6") (pintype "passive"))
    )
    (net (code "75") (name "unconnected-(U1-SDD2-Pad5)") (class "Default")
      (node (ref "U1") (pin "5") (pinfunction "SDD2_5") (pintype "passive"))
    )
    (net (code "76") (name "unconnected-(U1-SDD3-Pad4)") (class "Default")
      (node (ref "U1") (pin "4") (pinfunction "SDD3_4") (pintype "passive"))
    )
    (net (code "77") (name "unconnected-(U1-TX-Pad18)") (class "Default")
      (node (ref "U1") (pin "18") (pinfunction "TX_18") (pintype "passive"))
    )
  )
)
